# Control_Panel_Part2.net
KiCad netlist of a schematic drawn in Altium Designer
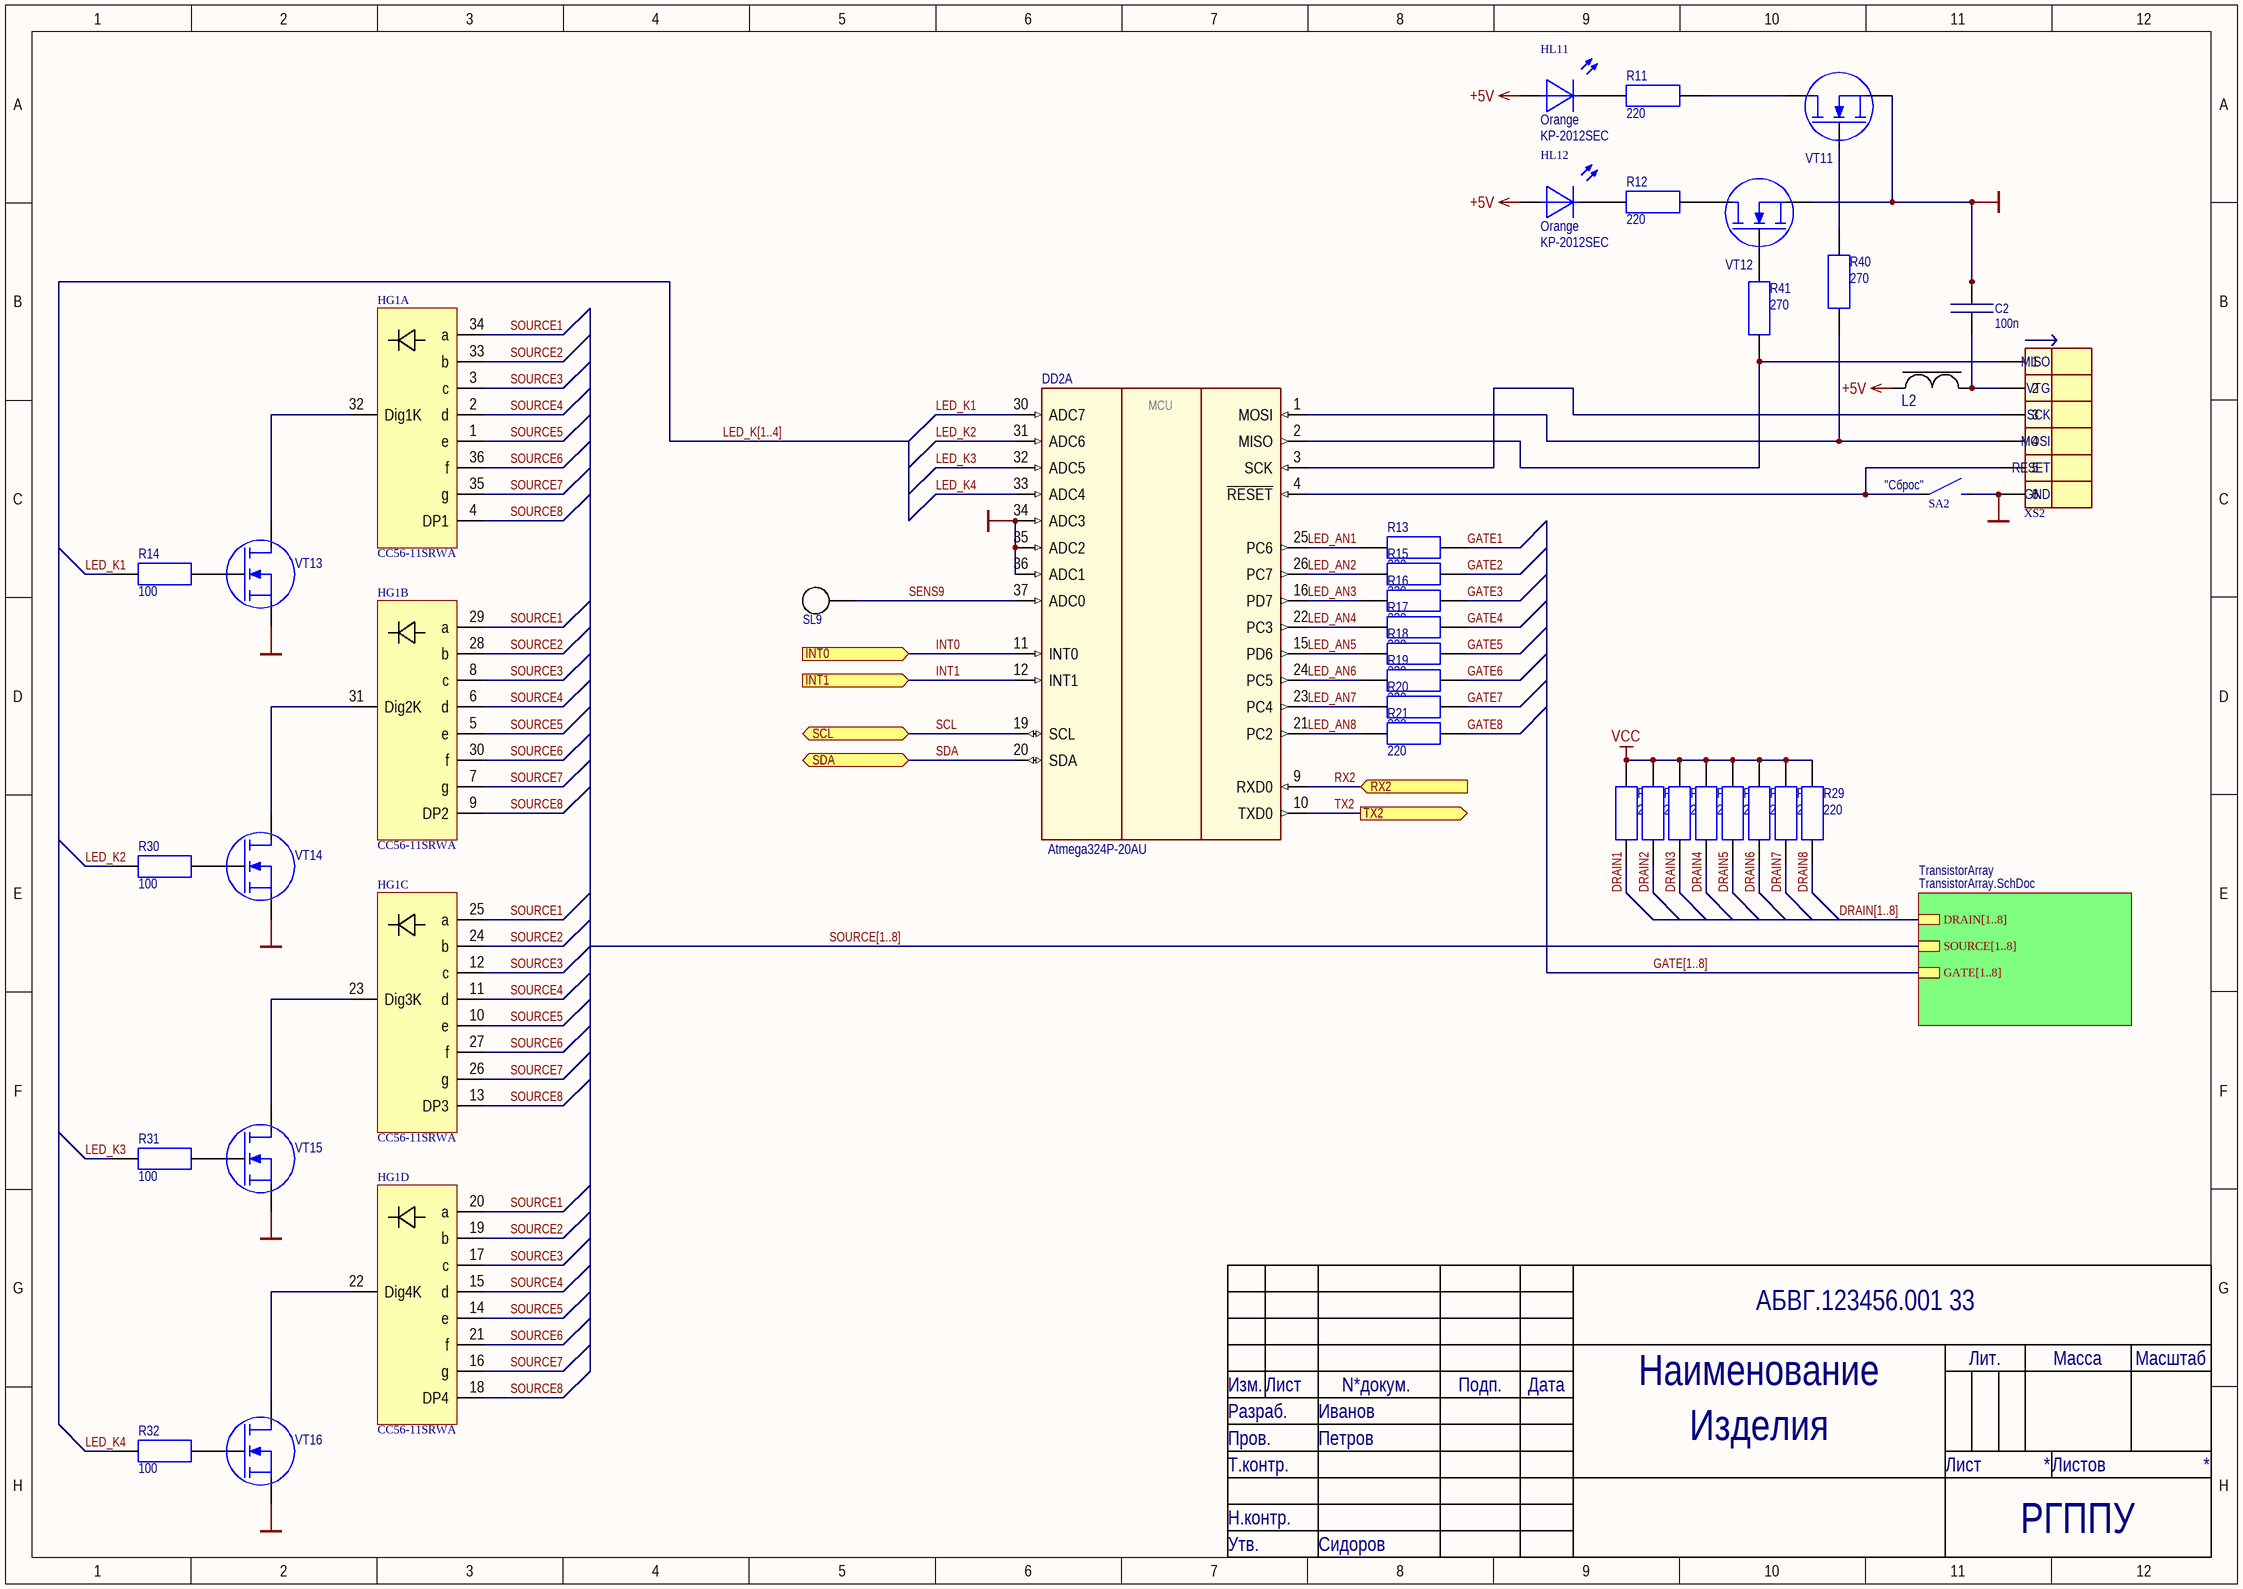
[diagram p0: Control_Panel_Part2.SchDoc]

(export (version "E")
  (design (tool "Eeschema 10.0.6"))
  (components
    (comp (ref "C2")
      (value "100n")
      (footprint "SMDRC0805")
      (description "Generic capasitor non-polar")
      (fields (field (name "PARTNUMBER") "Capacitor 0805 100n"))
      (libsource (lib "library") (part "Capacitor"))
    )
    (comp (ref "DD2")
      (value "Atmega324P-20AU")
      (footprint "Atmel Microcontroller 8-Bit Automotive AVR:44ML_M")
      (description "Microcontroller 8-bit")
      (fields (field (name "MANUFACTURER") "Atmel") (field (name "MANUFACTURERPARTNUMBER") "Atmega324P-20AU"))
      (libsource (lib "Microcontrollers") (part "Atmega324P-20AU"))
    )
    (comp (ref "HG1")
      (value "CC56-11SRWA")
      (footprint "Indicator:CC56-11SRWA")
      (fields (field (name "MANUFACTURER") "Kingbright"))
      (libsource (lib "Indicator") (part "CC56-11SRWA"))
    )
    (comp (ref "HL11")
      (value "Orange")
      (footprint "Indicator:DIOMELF2012M")
      (description "Diod LED SMD Orange")
      (fields (field (name "MANUFACTURERPARTNUMBER") "KP-2012SEC"))
      (libsource (lib "Indicator") (part "LED1_O"))
    )
    (comp (ref "HL12")
      (value "Orange")
      (footprint "Indicator:DIOMELF2012M")
      (description "Diod LED SMD Orange")
      (fields (field (name "MANUFACTURERPARTNUMBER") "KP-2012SEC"))
      (libsource (lib "Indicator") (part "LED1_O"))
    )
    (comp (ref "L2")
      (value "MPZ1608S181A")
      (footprint "Inductor:INDC0603X03M")
      (description "Ferrite Bead")
      (libsource (lib "Inductor") (part "Ferrite Bead"))
    )
    (comp (ref "R11")
      (value "220")
      (footprint "SMDRC0805")
      (description "Generic resistor")
      (fields (field (name "PARTNUMBER") "Resistor 0805 220"))
      (libsource (lib "") (part "Resistor_2"))
    )
    (comp (ref "R12")
      (value "220")
      (footprint "SMDRC0805")
      (description "Generic resistor")
      (fields (field (name "PARTNUMBER") "Resistor 0805 220"))
      (libsource (lib "") (part "Resistor_2"))
    )
    (comp (ref "R13")
      (value "220")
      (footprint "SMDRC0805")
      (description "Generic resistor")
      (fields (field (name "PARTNUMBER") "Resistor 0805 220"))
      (libsource (lib "library") (part "Resistor"))
    )
    (comp (ref "R14")
      (value "100")
      (footprint "SMDRC0805")
      (description "Generic resistor")
      (fields (field (name "PARTNUMBER") "Resistor 0805 100"))
      (libsource (lib "library") (part "Resistor"))
    )
    (comp (ref "R15")
      (value "220")
      (footprint "SMDRC0805")
      (description "Generic resistor")
      (fields (field (name "PARTNUMBER") "Resistor 0805 220"))
      (libsource (lib "library") (part "Resistor"))
    )
    (comp (ref "R16")
      (value "220")
      (footprint "SMDRC0805")
      (description "Generic resistor")
      (fields (field (name "PARTNUMBER") "Resistor 0805 220"))
      (libsource (lib "library") (part "Resistor"))
    )
    (comp (ref "R17")
      (value "220")
      (footprint "SMDRC0805")
      (description "Generic resistor")
      (fields (field (name "PARTNUMBER") "Resistor 0805 220"))
      (libsource (lib "library") (part "Resistor"))
    )
    (comp (ref "R18")
      (value "220")
      (footprint "SMDRC0805")
      (description "Generic resistor")
      (fields (field (name "PARTNUMBER") "Resistor 0805 220"))
      (libsource (lib "library") (part "Resistor"))
    )
    (comp (ref "R19")
      (value "220")
      (footprint "SMDRC0805")
      (description "Generic resistor")
      (fields (field (name "PARTNUMBER") "Resistor 0805 220"))
      (libsource (lib "library") (part "Resistor"))
    )
    (comp (ref "R20")
      (value "220")
      (footprint "SMDRC0805")
      (description "Generic resistor")
      (fields (field (name "PARTNUMBER") "Resistor 0805 220"))
      (libsource (lib "library") (part "Resistor"))
    )
    (comp (ref "R21")
      (value "220")
      (footprint "SMDRC0805")
      (description "Generic resistor")
      (fields (field (name "PARTNUMBER") "Resistor 0805 220"))
      (libsource (lib "library") (part "Resistor"))
    )
    (comp (ref "R22")
      (value "220")
      (footprint "SMDRC0805")
      (description "Generic resistor")
      (fields (field (name "PARTNUMBER") "Resistor 0805 220"))
      (libsource (lib "") (part "Resistor_1"))
    )
    (comp (ref "R23")
      (value "220")
      (footprint "SMDRC0805")
      (description "Generic resistor")
      (fields (field (name "PARTNUMBER") "Resistor 0805 220"))
      (libsource (lib "") (part "Resistor_1"))
    )
    (comp (ref "R24")
      (value "220")
      (footprint "SMDRC0805")
      (description "Generic resistor")
      (fields (field (name "PARTNUMBER") "Resistor 0805 220"))
      (libsource (lib "") (part "Resistor_1"))
    )
    (comp (ref "R25")
      (value "220")
      (footprint "SMDRC0805")
      (description "Generic resistor")
      (fields (field (name "PARTNUMBER") "Resistor 0805 220"))
      (libsource (lib "") (part "Resistor_1"))
    )
    (comp (ref "R26")
      (value "220")
      (footprint "SMDRC0805")
      (description "Generic resistor")
      (fields (field (name "PARTNUMBER") "Resistor 0805 220"))
      (libsource (lib "") (part "Resistor_1"))
    )
    (comp (ref "R27")
      (value "220")
      (footprint "SMDRC0805")
      (description "Generic resistor")
      (fields (field (name "PARTNUMBER") "Resistor 0805 220"))
      (libsource (lib "") (part "Resistor_1"))
    )
    (comp (ref "R28")
      (value "220")
      (footprint "SMDRC0805")
      (description "Generic resistor")
      (fields (field (name "PARTNUMBER") "Resistor 0805 220"))
      (libsource (lib "") (part "Resistor_1"))
    )
    (comp (ref "R29")
      (value "220")
      (footprint "SMDRC0805")
      (description "Generic resistor")
      (fields (field (name "PARTNUMBER") "Resistor 0805 220"))
      (libsource (lib "") (part "Resistor_1"))
    )
    (comp (ref "R30")
      (value "100")
      (footprint "SMDRC0805")
      (description "Generic resistor")
      (fields (field (name "PARTNUMBER") "Resistor 0805 100"))
      (libsource (lib "library") (part "Resistor"))
    )
    (comp (ref "R31")
      (value "100")
      (footprint "SMDRC0805")
      (description "Generic resistor")
      (fields (field (name "PARTNUMBER") "Resistor 0805 100"))
      (libsource (lib "library") (part "Resistor"))
    )
    (comp (ref "R32")
      (value "100")
      (footprint "SMDRC0805")
      (description "Generic resistor")
      (fields (field (name "PARTNUMBER") "Resistor 0805 100"))
      (libsource (lib "library") (part "Resistor"))
    )
    (comp (ref "R40")
      (value "270")
      (footprint "SMDRC0805")
      (description "Generic resistor")
      (fields (field (name "PARTNUMBER") "Resistor 0805 270"))
      (libsource (lib "") (part "Resistor_1"))
    )
    (comp (ref "R41")
      (value "270")
      (footprint "SMDRC0805")
      (description "Generic resistor")
      (fields (field (name "PARTNUMBER") "Resistor 0805 270"))
      (libsource (lib "") (part "Resistor_1"))
    )
    (comp (ref "SA2")
      (value "DTSM20-4.3")
      (footprint "Switch:DTSM20")
      (description "Switch open")
      (fields (field (name "MANUFACTURER") "Diptronics"))
      (libsource (lib "Switch") (part "Switch1_DTSM20-4.3"))
    )
    (comp (ref "SL9")
      (value "Touch_sensor")
      (footprint "Sensor:Bolt 6mm")
      (description "Bolt touch sensor")
      (libsource (lib "Sensor") (part "Touch_sensor"))
    )
    (comp (ref "VT11")
      (value "2N7002")
      (footprint "Standard:SOT23 (TO-236AB)")
      (description "60V, 300mA N-channel Trench MOSFET")
      (libsource (lib "Transistor") (part "2N7002 n-MOSFET"))
    )
    (comp (ref "VT12")
      (value "2N7002")
      (footprint "Standard:SOT23 (TO-236AB)")
      (description "60V, 300mA N-channel Trench MOSFET")
      (libsource (lib "Transistor") (part "2N7002 n-MOSFET"))
    )
    (comp (ref "VT13")
      (value "2N7002")
      (footprint "Standard:SOT23 (TO-236AB)")
      (description "60V, 300mA N-channel Trench MOSFET")
      (libsource (lib "Transistor") (part "2N7002 n-MOSFET"))
    )
    (comp (ref "VT14")
      (value "2N7002")
      (footprint "Standard:SOT23 (TO-236AB)")
      (description "60V, 300mA N-channel Trench MOSFET")
      (libsource (lib "Transistor") (part "2N7002 n-MOSFET"))
    )
    (comp (ref "VT15")
      (value "2N7002")
      (footprint "Standard:SOT23 (TO-236AB)")
      (description "60V, 300mA N-channel Trench MOSFET")
      (libsource (lib "Transistor") (part "2N7002 n-MOSFET"))
    )
    (comp (ref "VT16")
      (value "2N7002")
      (footprint "Standard:SOT23 (TO-236AB)")
      (description "60V, 300mA N-channel Trench MOSFET")
      (libsource (lib "Transistor") (part "2N7002 n-MOSFET"))
    )
    (comp (ref "XS2")
      (value "IDC-06M")
      (footprint "Connector:IDC-06M")
      (description "SPI connector")
      (libsource (lib "Connector") (part "Con6_M IDC-06M_SPI"))
    )
  )
  (nets
    (net (code "1") (name "+5V") (class "Default")
      (node (ref "HL11") (pin "1") (pinfunction "1_1") (pintype "passive"))
      (node (ref "HL12") (pin "1") (pinfunction "1_1") (pintype "passive"))
      (node (ref "L2") (pin "1") (pinfunction "1_1") (pintype "passive"))
    )
    (net (code "2") (name "/DRAIN1") (class "Default")
      (node (ref "R22") (pin "1") (pinfunction "1_1") (pintype "passive"))
    )
    (net (code "3") (name "/DRAIN2") (class "Default")
      (node (ref "R23") (pin "1") (pinfunction "1_1") (pintype "passive"))
    )
    (net (code "4") (name "/DRAIN3") (class "Default")
      (node (ref "R24") (pin "1") (pinfunction "1_1") (pintype "passive"))
    )
    (net (code "5") (name "/DRAIN4") (class "Default")
      (node (ref "R25") (pin "1") (pinfunction "1_1") (pintype "passive"))
    )
    (net (code "6") (name "/DRAIN5") (class "Default")
      (node (ref "R26") (pin "1") (pinfunction "1_1") (pintype "passive"))
    )
    (net (code "7") (name "/DRAIN6") (class "Default")
      (node (ref "R27") (pin "1") (pinfunction "1_1") (pintype "passive"))
    )
    (net (code "8") (name "/DRAIN7") (class "Default")
      (node (ref "R28") (pin "1") (pinfunction "1_1") (pintype "passive"))
    )
    (net (code "9") (name "/DRAIN8") (class "Default")
      (node (ref "R29") (pin "1") (pinfunction "1_1") (pintype "passive"))
    )
    (net (code "11") (name "/GATE1") (class "Default")
      (node (ref "R13") (pin "2") (pinfunction "2_2") (pintype "passive"))
    )
    (net (code "12") (name "/GATE2") (class "Default")
      (node (ref "R15") (pin "2") (pinfunction "2_2") (pintype "passive"))
    )
    (net (code "13") (name "/GATE3") (class "Default")
      (node (ref "R16") (pin "2") (pinfunction "2_2") (pintype "passive"))
    )
    (net (code "14") (name "/GATE4") (class "Default")
      (node (ref "R17") (pin "2") (pinfunction "2_2") (pintype "passive"))
    )
    (net (code "15") (name "/GATE5") (class "Default")
      (node (ref "R18") (pin "2") (pinfunction "2_2") (pintype "passive"))
    )
    (net (code "16") (name "/GATE6") (class "Default")
      (node (ref "R19") (pin "2") (pinfunction "2_2") (pintype "passive"))
    )
    (net (code "17") (name "/GATE7") (class "Default")
      (node (ref "R20") (pin "2") (pinfunction "2_2") (pintype "passive"))
    )
    (net (code "18") (name "/GATE8") (class "Default")
      (node (ref "R21") (pin "2") (pinfunction "2_2") (pintype "passive"))
    )
    (net (code "20") (name "/INT0") (class "Default")
      (node (ref "DD2") (pin "11") (pinfunction "INT0_11") (pintype "input"))
    )
    (net (code "21") (name "/INT1") (class "Default")
      (node (ref "DD2") (pin "12") (pinfunction "INT1_12") (pintype "input"))
    )
    (net (code "22") (name "/LED_AN1") (class "Default")
      (node (ref "DD2") (pin "25") (pinfunction "PC6_25") (pintype "output"))
      (node (ref "R13") (pin "1") (pinfunction "1_1") (pintype "passive"))
    )
    (net (code "23") (name "/LED_AN2") (class "Default")
      (node (ref "DD2") (pin "26") (pinfunction "PC7_26") (pintype "output"))
      (node (ref "R15") (pin "1") (pinfunction "1_1") (pintype "passive"))
    )
    (net (code "24") (name "/LED_AN3") (class "Default")
      (node (ref "DD2") (pin "16") (pinfunction "PD7_16") (pintype "output"))
      (node (ref "R16") (pin "1") (pinfunction "1_1") (pintype "passive"))
    )
    (net (code "25") (name "/LED_AN4") (class "Default")
      (node (ref "DD2") (pin "22") (pinfunction "PC3_22") (pintype "output"))
      (node (ref "R17") (pin "1") (pinfunction "1_1") (pintype "passive"))
    )
    (net (code "26") (name "/LED_AN5") (class "Default")
      (node (ref "DD2") (pin "15") (pinfunction "PD6_15") (pintype "output"))
      (node (ref "R18") (pin "1") (pinfunction "1_1") (pintype "passive"))
    )
    (net (code "27") (name "/LED_AN6") (class "Default")
      (node (ref "DD2") (pin "24") (pinfunction "PC5_24") (pintype "output"))
      (node (ref "R19") (pin "1") (pinfunction "1_1") (pintype "passive"))
    )
    (net (code "28") (name "/LED_AN7") (class "Default")
      (node (ref "DD2") (pin "23") (pinfunction "PC4_23") (pintype "output"))
      (node (ref "R20") (pin "1") (pinfunction "1_1") (pintype "passive"))
    )
    (net (code "29") (name "/LED_AN8") (class "Default")
      (node (ref "DD2") (pin "21") (pinfunction "PC2_21") (pintype "output"))
      (node (ref "R21") (pin "1") (pinfunction "1_1") (pintype "passive"))
    )
    (net (code "30") (name "/LED_K1") (class "Default")
      (node (ref "DD2") (pin "30") (pinfunction "ADC7_30") (pintype "input"))
      (node (ref "R14") (pin "1") (pinfunction "1_1") (pintype "passive"))
    )
    (net (code "31") (name "/LED_K2") (class "Default")
      (node (ref "DD2") (pin "31") (pinfunction "ADC6_31") (pintype "input"))
      (node (ref "R30") (pin "1") (pinfunction "1_1") (pintype "passive"))
    )
    (net (code "32") (name "/LED_K3") (class "Default")
      (node (ref "DD2") (pin "32") (pinfunction "ADC5_32") (pintype "input"))
      (node (ref "R31") (pin "1") (pinfunction "1_1") (pintype "passive"))
    )
    (net (code "33") (name "/LED_K4") (class "Default")
      (node (ref "DD2") (pin "33") (pinfunction "ADC4_33") (pintype "input"))
      (node (ref "R32") (pin "1") (pinfunction "1_1") (pintype "passive"))
    )
    (net (code "35") (name "/RX2") (class "Default")
      (node (ref "DD2") (pin "9") (pinfunction "RXD0_9") (pintype "input"))
    )
    (net (code "36") (name "/SCL") (class "Default")
      (node (ref "DD2") (pin "19") (pinfunction "SCL_19") (pintype "bidirectional"))
    )
    (net (code "37") (name "/SDA") (class "Default")
      (node (ref "DD2") (pin "20") (pinfunction "SDA_20") (pintype "bidirectional"))
    )
    (net (code "38") (name "/SENS9") (class "Default")
      (node (ref "DD2") (pin "37") (pinfunction "ADC0_37") (pintype "input"))
      (node (ref "SL9") (pin "1") (pinfunction "1_1") (pintype "passive"))
    )
    (net (code "39") (name "/SOURCE1") (class "Default")
      (node (ref "HG1") (pin "20") (pinfunction "a_20") (pintype "passive"))
      (node (ref "HG1") (pin "25") (pinfunction "a_25") (pintype "passive"))
      (node (ref "HG1") (pin "29") (pinfunction "a_29") (pintype "passive"))
      (node (ref "HG1") (pin "34") (pinfunction "a_34") (pintype "passive"))
    )
    (net (code "40") (name "/SOURCE2") (class "Default")
      (node (ref "HG1") (pin "19") (pinfunction "b_19") (pintype "passive"))
      (node (ref "HG1") (pin "24") (pinfunction "b_24") (pintype "passive"))
      (node (ref "HG1") (pin "28") (pinfunction "b_28") (pintype "passive"))
      (node (ref "HG1") (pin "33") (pinfunction "b_33") (pintype "passive"))
    )
    (net (code "41") (name "/SOURCE3") (class "Default")
      (node (ref "HG1") (pin "12") (pinfunction "c_12") (pintype "passive"))
      (node (ref "HG1") (pin "17") (pinfunction "c_17") (pintype "passive"))
      (node (ref "HG1") (pin "3") (pinfunction "c_3") (pintype "passive"))
      (node (ref "HG1") (pin "8") (pinfunction "c_8") (pintype "passive"))
    )
    (net (code "42") (name "/SOURCE4") (class "Default")
      (node (ref "HG1") (pin "11") (pinfunction "d_11") (pintype "passive"))
      (node (ref "HG1") (pin "15") (pinfunction "d_15") (pintype "passive"))
      (node (ref "HG1") (pin "2") (pinfunction "d_2") (pintype "passive"))
      (node (ref "HG1") (pin "6") (pinfunction "d_6") (pintype "passive"))
    )
    (net (code "43") (name "/SOURCE5") (class "Default")
      (node (ref "HG1") (pin "1") (pinfunction "e_1") (pintype "passive"))
      (node (ref "HG1") (pin "10") (pinfunction "e_10") (pintype "passive"))
      (node (ref "HG1") (pin "14") (pinfunction "e_14") (pintype "passive"))
      (node (ref "HG1") (pin "5") (pinfunction "e_5") (pintype "passive"))
    )
    (net (code "44") (name "/SOURCE6") (class "Default")
      (node (ref "HG1") (pin "21") (pinfunction "f_21") (pintype "passive"))
      (node (ref "HG1") (pin "27") (pinfunction "f_27") (pintype "passive"))
      (node (ref "HG1") (pin "30") (pinfunction "f_30") (pintype "passive"))
      (node (ref "HG1") (pin "36") (pinfunction "f_36") (pintype "passive"))
    )
    (net (code "45") (name "/SOURCE7") (class "Default")
      (node (ref "HG1") (pin "16") (pinfunction "g_16") (pintype "passive"))
      (node (ref "HG1") (pin "26") (pinfunction "g_26") (pintype "passive"))
      (node (ref "HG1") (pin "35") (pinfunction "g_35") (pintype "passive"))
      (node (ref "HG1") (pin "7") (pinfunction "g_7") (pintype "passive"))
    )
    (net (code "46") (name "/SOURCE8") (class "Default")
      (node (ref "HG1") (pin "13") (pinfunction "DP3_13") (pintype "passive"))
      (node (ref "HG1") (pin "18") (pinfunction "DP4_18") (pintype "passive"))
      (node (ref "HG1") (pin "4") (pinfunction "DP1_4") (pintype "passive"))
      (node (ref "HG1") (pin "9") (pinfunction "DP2_9") (pintype "passive"))
    )
    (net (code "48") (name "/TX2") (class "Default")
      (node (ref "DD2") (pin "10") (pinfunction "TXD0_10") (pintype "output"))
    )
    (net (code "49") (name "GND") (class "Default")
      (node (ref "C2") (pin "2") (pintype "passive"))
      (node (ref "DD2") (pin "34") (pinfunction "ADC3_34") (pintype "input"))
      (node (ref "DD2") (pin "35") (pinfunction "ADC2_35") (pintype "input"))
      (node (ref "DD2") (pin "36") (pinfunction "ADC1_36") (pintype "input"))
      (node (ref "SA2") (pin "2") (pinfunction "2_2") (pintype "passive"))
      (node (ref "VT11") (pin "2") (pinfunction "S_2") (pintype "passive"))
      (node (ref "VT12") (pin "2") (pinfunction "S_2") (pintype "passive"))
      (node (ref "VT13") (pin "2") (pinfunction "S_2") (pintype "passive"))
      (node (ref "VT14") (pin "2") (pinfunction "S_2") (pintype "passive"))
      (node (ref "VT15") (pin "2") (pinfunction "S_2") (pintype "passive"))
      (node (ref "VT16") (pin "2") (pinfunction "S_2") (pintype "passive"))
      (node (ref "XS2") (pin "6") (pinfunction "6_6") (pintype "passive"))
    )
    (net (code "50") (name "Net-(C2-Pad1)") (class "Default")
      (node (ref "C2") (pin "1") (pintype "passive"))
      (node (ref "L2") (pin "2") (pinfunction "2_2") (pintype "passive"))
      (node (ref "XS2") (pin "2") (pinfunction "2_2") (pintype "passive"))
    )
    (net (code "51") (name "Net-(DD2A-MISO)") (class "Default")
      (node (ref "DD2") (pin "2") (pinfunction "MISO_2") (pintype "output"))
      (node (ref "R41") (pin "1") (pinfunction "1_1") (pintype "passive"))
      (node (ref "XS2") (pin "1") (pinfunction "1_1") (pintype "passive"))
    )
    (net (code "52") (name "Net-(DD2A-MOSI)") (class "Default")
      (node (ref "DD2") (pin "1") (pinfunction "MOSI_1") (pintype "input"))
      (node (ref "R40") (pin "1") (pinfunction "1_1") (pintype "passive"))
      (node (ref "XS2") (pin "4") (pinfunction "4_4") (pintype "passive"))
    )
    (net (code "53") (name "Net-(DD2A-SCK)") (class "Default")
      (node (ref "DD2") (pin "3") (pinfunction "SCK_3") (pintype "input"))
      (node (ref "XS2") (pin "3") (pinfunction "3_3") (pintype "passive"))
    )
    (net (code "54") (name "Net-(DD2A-~{RESET})") (class "Default")
      (node (ref "DD2") (pin "4") (pinfunction "~{RESET}_4") (pintype "input"))
      (node (ref "SA2") (pin "1") (pinfunction "1_1") (pintype "passive"))
      (node (ref "XS2") (pin "5") (pinfunction "5_5") (pintype "passive"))
    )
    (net (code "55") (name "Net-(HG1A-Dig1K)") (class "Default")
      (node (ref "HG1") (pin "32") (pinfunction "Dig1K_32") (pintype "passive"))
      (node (ref "VT13") (pin "3") (pinfunction "D_3") (pintype "passive"))
    )
    (net (code "56") (name "Net-(HG1B-Dig2K)") (class "Default")
      (node (ref "HG1") (pin "31") (pinfunction "Dig2K_31") (pintype "passive"))
      (node (ref "VT14") (pin "3") (pinfunction "D_3") (pintype "passive"))
    )
    (net (code "57") (name "Net-(HG1C-Dig3K)") (class "Default")
      (node (ref "HG1") (pin "23") (pinfunction "Dig3K_23") (pintype "passive"))
      (node (ref "VT15") (pin "3") (pinfunction "D_3") (pintype "passive"))
    )
    (net (code "58") (name "Net-(HG1D-Dig4K)") (class "Default")
      (node (ref "HG1") (pin "22") (pinfunction "Dig4K_22") (pintype "passive"))
      (node (ref "VT16") (pin "3") (pinfunction "D_3") (pintype "passive"))
    )
    (net (code "59") (name "Net-(HL11-Pad2)") (class "Default")
      (node (ref "HL11") (pin "2") (pinfunction "2_2") (pintype "passive"))
      (node (ref "R11") (pin "2") (pinfunction "2_2") (pintype "passive"))
    )
    (net (code "60") (name "Net-(HL12-Pad2)") (class "Default")
      (node (ref "HL12") (pin "2") (pinfunction "2_2") (pintype "passive"))
      (node (ref "R12") (pin "2") (pinfunction "2_2") (pintype "passive"))
    )
    (net (code "61") (name "Net-(VT11-D)") (class "Default")
      (node (ref "R11") (pin "1") (pinfunction "1_1") (pintype "passive"))
      (node (ref "VT11") (pin "3") (pinfunction "D_3") (pintype "passive"))
    )
    (net (code "62") (name "Net-(VT11-G)") (class "Default")
      (node (ref "R40") (pin "2") (pinfunction "2_2") (pintype "passive"))
      (node (ref "VT11") (pin "1") (pinfunction "G_1") (pintype "passive"))
    )
    (net (code "63") (name "Net-(VT12-D)") (class "Default")
      (node (ref "R12") (pin "1") (pinfunction "1_1") (pintype "passive"))
      (node (ref "VT12") (pin "3") (pinfunction "D_3") (pintype "passive"))
    )
    (net (code "64") (name "Net-(VT12-G)") (class "Default")
      (node (ref "R41") (pin "2") (pinfunction "2_2") (pintype "passive"))
      (node (ref "VT12") (pin "1") (pinfunction "G_1") (pintype "passive"))
    )
    (net (code "65") (name "Net-(VT13-G)") (class "Default")
      (node (ref "R14") (pin "2") (pinfunction "2_2") (pintype "passive"))
      (node (ref "VT13") (pin "1") (pinfunction "G_1") (pintype "passive"))
    )
    (net (code "66") (name "Net-(VT14-G)") (class "Default")
      (node (ref "R30") (pin "2") (pinfunction "2_2") (pintype "passive"))
      (node (ref "VT14") (pin "1") (pinfunction "G_1") (pintype "passive"))
    )
    (net (code "67") (name "Net-(VT15-G)") (class "Default")
      (node (ref "R31") (pin "2") (pinfunction "2_2") (pintype "passive"))
      (node (ref "VT15") (pin "1") (pinfunction "G_1") (pintype "passive"))
    )
    (net (code "68") (name "Net-(VT16-G)") (class "Default")
      (node (ref "R32") (pin "2") (pinfunction "2_2") (pintype "passive"))
      (node (ref "VT16") (pin "1") (pinfunction "G_1") (pintype "passive"))
    )
    (net (code "69") (name "VCC") (class "Default")
      (node (ref "R22") (pin "2") (pinfunction "2_2") (pintype "passive"))
      (node (ref "R23") (pin "2") (pinfunction "2_2") (pintype "passive"))
      (node (ref "R24") (pin "2") (pinfunction "2_2") (pintype "passive"))
      (node (ref "R25") (pin "2") (pinfunction "2_2") (pintype "passive"))
      (node (ref "R26") (pin "2") (pinfunction "2_2") (pintype "passive"))
      (node (ref "R27") (pin "2") (pinfunction "2_2") (pintype "passive"))
      (node (ref "R28") (pin "2") (pinfunction "2_2") (pintype "passive"))
      (node (ref "R29") (pin "2") (pinfunction "2_2") (pintype "passive"))
    )
  )
)
